# LFR_A_v2.net
KiCad netlist of a schematic drawn in Altium Designer
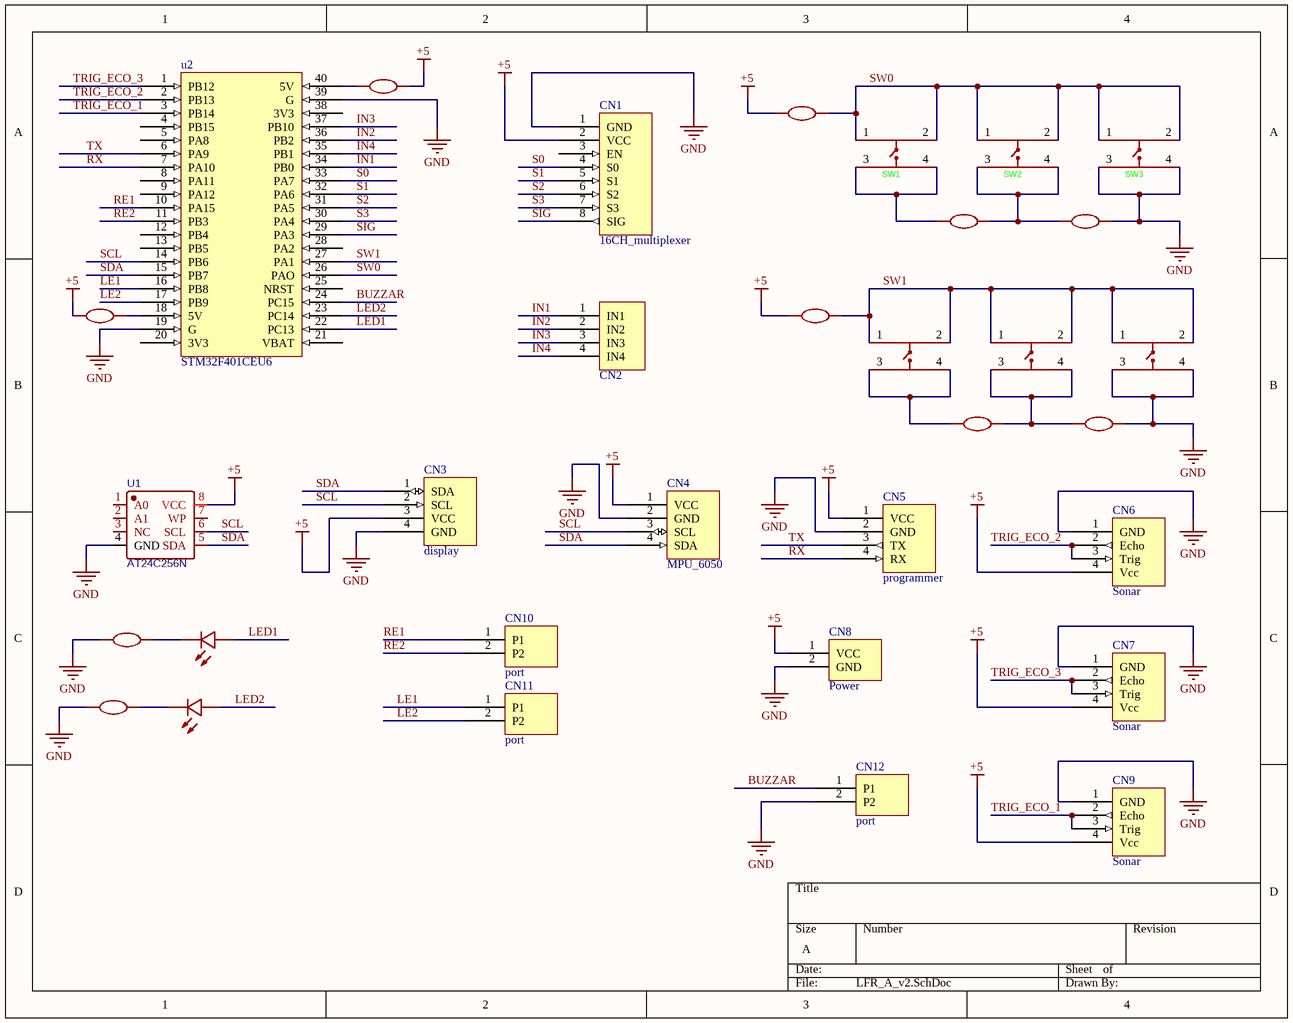
[diagram p0: LFR_A_v2.SchDoc]

(export (version "E")
  (design (tool "Eeschema 10.0.6"))
  (components
    (comp (ref "CN1")
      (value "16CH_multiplexer")
      (footprint "16CH_MUX")
      (libsource (lib "Schlib1") (part "16CH_multiplexer"))
    )
    (comp (ref "CN2") (value "M_Driver") (footprint "M_driver") (libsource (lib "Schlib1") (part "M_Driver")))
    (comp (ref "CN3") (value "display") (footprint "display") (libsource (lib "Schlib1") (part "display")))
    (comp (ref "CN4") (value "MPU_6050") (footprint "mpu_6050") (libsource (lib "Schlib1") (part "MPU_6050")))
    (comp (ref "CN5")
      (value "programmer")
      (footprint "Sonar")
      (libsource (lib "Schlib1") (part "programmer"))
    )
    (comp (ref "CN6") (value "Sonar") (footprint "Sonar") (libsource (lib "Schlib1") (part "Sonar")))
    (comp (ref "CN7") (value "Sonar") (footprint "Sonar") (libsource (lib "Schlib1") (part "Sonar")))
    (comp (ref "CN8") (value "Power") (footprint "power") (libsource (lib "Schlib1") (part "Power")))
    (comp (ref "CN9") (value "Sonar") (footprint "Sonar") (libsource (lib "Schlib1") (part "Sonar")))
    (comp (ref "CN10") (value "port") (footprint "power") (libsource (lib "Schlib1") (part "port")))
    (comp (ref "CN11") (value "port") (footprint "power") (libsource (lib "Schlib1") (part "port")))
    (comp (ref "CN12") (value "port") (footprint "power") (libsource (lib "Schlib1") (part "port")))
    (comp (ref "LED1")
      (value "333-2SURD/S530-A3")
      (footprint "LED-TH_BD5.9-P2.54-RD_RED")
      (fields (field (name "MANUFACTURER") "EVERLIGHT(亿光)"))
      (libsource (lib "Schlib1") (part "LED"))
    )
    (comp (ref "LED2")
      (value "333-2SURD/S530-A3")
      (footprint "LED-TH_BD5.9-P2.54-RD_RED")
      (fields (field (name "MANUFACTURER") "EVERLIGHT(亿光)"))
      (libsource (lib "Schlib1") (part "LED"))
    )
    (comp (ref "R1")
      (value "10kΩ")
      (footprint "regsistor")
      (fields
        (field (name "MANUFACTURER") "VISHAY(威世)")
        (field (name "MANUFACTURER PART") "MBB02070C1002FCT00")
        (field (name "TOLERANCE") "±1%")
      )
      (libsource (lib "Schlib1") (part "reg_10k"))
    )
    (comp (ref "R2")
      (value "10kΩ")
      (footprint "regsistor")
      (fields
        (field (name "MANUFACTURER") "VISHAY(威世)")
        (field (name "MANUFACTURER PART") "MBB02070C1002FCT00")
        (field (name "TOLERANCE") "±1%")
      )
      (libsource (lib "Schlib1") (part "reg_10k"))
    )
    (comp (ref "R3")
      (value "10kΩ")
      (footprint "regsistor")
      (fields
        (field (name "MANUFACTURER") "VISHAY(威世)")
        (field (name "MANUFACTURER PART") "MBB02070C1002FCT00")
        (field (name "TOLERANCE") "±1%")
      )
      (libsource (lib "Schlib1") (part "reg_10k"))
    )
    (comp (ref "R4")
      (value "10kΩ")
      (footprint "regsistor")
      (fields
        (field (name "MANUFACTURER") "VISHAY(威世)")
        (field (name "MANUFACTURER PART") "MBB02070C1002FCT00")
        (field (name "TOLERANCE") "±1%")
      )
      (libsource (lib "Schlib1") (part "reg_10k"))
    )
    (comp (ref "R5")
      (value "10kΩ")
      (footprint "regsistor")
      (fields
        (field (name "MANUFACTURER") "VISHAY(威世)")
        (field (name "MANUFACTURER PART") "MBB02070C1002FCT00")
        (field (name "TOLERANCE") "±1%")
      )
      (libsource (lib "Schlib1") (part "reg_10k"))
    )
    (comp (ref "R6")
      (value "10kΩ")
      (footprint "regsistor")
      (fields
        (field (name "MANUFACTURER") "VISHAY(威世)")
        (field (name "MANUFACTURER PART") "MBB02070C1002FCT00")
        (field (name "TOLERANCE") "±1%")
      )
      (libsource (lib "Schlib1") (part "reg_10k"))
    )
    (comp (ref "R7")
      (value "10kΩ")
      (footprint "regsistor")
      (fields
        (field (name "MANUFACTURER") "VISHAY(威世)")
        (field (name "MANUFACTURER PART") "MBB02070C1002FCT00")
        (field (name "TOLERANCE") "±1%")
      )
      (libsource (lib "Schlib1") (part "reg_10k"))
    )
    (comp (ref "R8")
      (value "10kΩ")
      (footprint "regsistor")
      (fields
        (field (name "MANUFACTURER") "VISHAY(威世)")
        (field (name "MANUFACTURER PART") "MBB02070C1002FCT00")
        (field (name "TOLERANCE") "±1%")
      )
      (libsource (lib "Schlib1") (part "reg_10k"))
    )
    (comp (ref "R9")
      (value "10kΩ")
      (footprint "regsistor")
      (fields
        (field (name "MANUFACTURER") "VISHAY(威世)")
        (field (name "MANUFACTURER PART") "MBB02070C1002FCT00")
        (field (name "TOLERANCE") "±1%")
      )
      (libsource (lib "Schlib1") (part "reg_10k"))
    )
    (comp (ref "R10")
      (value "10kΩ")
      (footprint "regsistor")
      (fields
        (field (name "MANUFACTURER") "VISHAY(威世)")
        (field (name "MANUFACTURER PART") "MBB02070C1002FCT00")
        (field (name "TOLERANCE") "±1%")
      )
      (libsource (lib "Schlib1") (part "reg_10k"))
    )
    (comp (ref "SW1")
      (value "1825910-7")
      (footprint "button")
      (fields (field (name "MANUFACTURER") "TE Connectivity(泰科电子)"))
      (libsource (lib "Schlib1") (part "button"))
    )
    (comp (ref "SW2")
      (value "1825910-7")
      (footprint "button")
      (fields (field (name "MANUFACTURER") "TE Connectivity(泰科电子)"))
      (libsource (lib "Schlib1") (part "button"))
    )
    (comp (ref "SW3")
      (value "1825910-7")
      (footprint "button")
      (fields (field (name "MANUFACTURER") "TE Connectivity(泰科电子)"))
      (libsource (lib "Schlib1") (part "button"))
    )
    (comp (ref "SW4")
      (value "1825910-7")
      (footprint "button")
      (fields (field (name "MANUFACTURER") "TE Connectivity(泰科电子)"))
      (libsource (lib "Schlib1") (part "button"))
    )
    (comp (ref "SW5")
      (value "1825910-7")
      (footprint "button")
      (fields (field (name "MANUFACTURER") "TE Connectivity(泰科电子)"))
      (libsource (lib "Schlib1") (part "button"))
    )
    (comp (ref "SW6")
      (value "1825910-7")
      (footprint "button")
      (fields (field (name "MANUFACTURER") "TE Connectivity(泰科电子)"))
      (libsource (lib "Schlib1") (part "button"))
    )
    (comp (ref "U1")
      (value "AT24C256N")
      (footprint "DIP-8_L9.8-W6.6-P2.54-LS7.6-BL")
      (fields (field (name "MANUFACTURER") "HGSEMI(华冠)") (field (name "CONTRIBUTOR") "LCSC"))
      (libsource (lib "Schlib1") (part "AT24C256N"))
    )
    (comp (ref "u2")
      (value "STM32F401CEU6")
      (footprint "STM32F411CE")
      (libsource (lib "Schlib1") (part "STM32F401CEU6"))
    )
  )
  (nets
    (net (code "1") (name "+5") (class "Default")
      (node (ref "CN1") (pin "2") (pinfunction "VCC_2") (pintype "power_in"))
      (node (ref "CN3") (pin "3") (pinfunction "VCC_3") (pintype "power_in"))
      (node (ref "CN4") (pin "1") (pinfunction "VCC_1") (pintype "power_in"))
      (node (ref "CN5") (pin "1") (pinfunction "VCC_1") (pintype "power_in"))
      (node (ref "CN6") (pin "4") (pinfunction "Vcc_4") (pintype "power_in"))
      (node (ref "CN7") (pin "4") (pinfunction "Vcc_4") (pintype "power_in"))
      (node (ref "CN8") (pin "1") (pinfunction "VCC_1") (pintype "power_in"))
      (node (ref "CN9") (pin "4") (pinfunction "Vcc_4") (pintype "power_in"))
      (node (ref "R1") (pin "1") (pinfunction "1_1") (pintype "passive"))
      (node (ref "R4") (pin "1") (pinfunction "1_1") (pintype "passive"))
      (node (ref "R7") (pin "2") (pinfunction "2_2") (pintype "passive"))
      (node (ref "R8") (pin "2") (pinfunction "2_2") (pintype "passive"))
      (node (ref "U1") (pin "8") (pinfunction "VCC_8") (pintype "passive"))
    )
    (net (code "2") (name "/BUZZAR") (class "Default")
      (node (ref "CN12") (pin "1") (pinfunction "P1_1") (pintype "passive"))
      (node (ref "u2") (pin "24") (pinfunction "PC15_24") (pintype "input"))
    )
    (net (code "3") (name "/IN1") (class "Default")
      (node (ref "CN2") (pin "1") (pinfunction "IN1_1") (pintype "passive"))
      (node (ref "u2") (pin "34") (pinfunction "PB0_34") (pintype "input"))
    )
    (net (code "4") (name "/IN2") (class "Default")
      (node (ref "CN2") (pin "2") (pinfunction "IN2_2") (pintype "passive"))
      (node (ref "u2") (pin "36") (pinfunction "PB2_36") (pintype "input"))
    )
    (net (code "5") (name "/IN3") (class "Default")
      (node (ref "CN2") (pin "3") (pinfunction "IN3_3") (pintype "passive"))
      (node (ref "u2") (pin "37") (pinfunction "PB10_37") (pintype "input"))
    )
    (net (code "6") (name "/IN4") (class "Default")
      (node (ref "CN2") (pin "4") (pinfunction "IN4_4") (pintype "passive"))
      (node (ref "u2") (pin "35") (pinfunction "PB1_35") (pintype "input"))
    )
    (net (code "7") (name "/LE1") (class "Default")
      (node (ref "CN11") (pin "1") (pinfunction "P1_1") (pintype "passive"))
      (node (ref "u2") (pin "16") (pinfunction "PB8_16") (pintype "input"))
    )
    (net (code "8") (name "/LE2") (class "Default")
      (node (ref "CN11") (pin "2") (pinfunction "P2_2") (pintype "passive"))
      (node (ref "u2") (pin "17") (pinfunction "PB9_17") (pintype "input"))
    )
    (net (code "9") (name "/LED1") (class "Default")
      (node (ref "LED1") (pin "2") (pinfunction "A_2") (pintype "passive"))
      (node (ref "u2") (pin "22") (pinfunction "PC13_22") (pintype "input"))
    )
    (net (code "10") (name "/LED2") (class "Default")
      (node (ref "LED2") (pin "2") (pinfunction "A_2") (pintype "passive"))
      (node (ref "u2") (pin "23") (pinfunction "PC14_23") (pintype "input"))
    )
    (net (code "11") (name "/RE1") (class "Default")
      (node (ref "CN10") (pin "1") (pinfunction "P1_1") (pintype "passive"))
      (node (ref "u2") (pin "10") (pinfunction "PA15_10") (pintype "input"))
    )
    (net (code "12") (name "/RE2") (class "Default")
      (node (ref "CN10") (pin "2") (pinfunction "P2_2") (pintype "passive"))
      (node (ref "u2") (pin "11") (pinfunction "PB3_11") (pintype "input"))
    )
    (net (code "13") (name "/RX") (class "Default")
      (node (ref "CN5") (pin "4") (pinfunction "RX_4") (pintype "input"))
      (node (ref "u2") (pin "7") (pinfunction "PA10_7") (pintype "input"))
    )
    (net (code "14") (name "/S0") (class "Default")
      (node (ref "CN1") (pin "4") (pinfunction "S0_4") (pintype "input"))
      (node (ref "u2") (pin "33") (pinfunction "PA7_33") (pintype "input"))
    )
    (net (code "15") (name "/S1") (class "Default")
      (node (ref "CN1") (pin "5") (pinfunction "S1_5") (pintype "input"))
      (node (ref "u2") (pin "32") (pinfunction "PA6_32") (pintype "input"))
    )
    (net (code "16") (name "/S2") (class "Default")
      (node (ref "CN1") (pin "6") (pinfunction "S2_6") (pintype "input"))
      (node (ref "u2") (pin "31") (pinfunction "PA5_31") (pintype "input"))
    )
    (net (code "17") (name "/S3") (class "Default")
      (node (ref "CN1") (pin "7") (pinfunction "S3_7") (pintype "input"))
      (node (ref "u2") (pin "30") (pinfunction "PA4_30") (pintype "input"))
    )
    (net (code "18") (name "/SCL") (class "Default")
      (node (ref "CN3") (pin "2") (pinfunction "SCL_2") (pintype "input"))
      (node (ref "CN4") (pin "3") (pinfunction "SCL_3") (pintype "bidirectional"))
      (node (ref "U1") (pin "6") (pinfunction "SCL_6") (pintype "passive"))
      (node (ref "u2") (pin "14") (pinfunction "PB6_14") (pintype "input"))
    )
    (net (code "19") (name "/SDA") (class "Default")
      (node (ref "CN3") (pin "1") (pinfunction "SDA_1") (pintype "bidirectional"))
      (node (ref "CN4") (pin "4") (pinfunction "SDA_4") (pintype "input"))
      (node (ref "U1") (pin "5") (pinfunction "SDA_5") (pintype "passive"))
      (node (ref "u2") (pin "15") (pinfunction "PB7_15") (pintype "input"))
    )
    (net (code "20") (name "/SIG") (class "Default")
      (node (ref "CN1") (pin "8") (pinfunction "SIG_8") (pintype "output"))
      (node (ref "u2") (pin "29") (pinfunction "PA3_29") (pintype "input"))
    )
    (net (code "21") (name "/SW0") (class "Default")
      (node (ref "R1") (pin "2") (pinfunction "2_2") (pintype "passive"))
      (node (ref "SW1") (pin "1") (pinfunction "1_1") (pintype "passive"))
      (node (ref "SW1") (pin "2") (pinfunction "2_2") (pintype "passive"))
      (node (ref "SW2") (pin "1") (pinfunction "1_1") (pintype "passive"))
      (node (ref "SW2") (pin "2") (pinfunction "2_2") (pintype "passive"))
      (node (ref "SW3") (pin "1") (pinfunction "1_1") (pintype "passive"))
      (node (ref "SW3") (pin "2") (pinfunction "2_2") (pintype "passive"))
      (node (ref "u2") (pin "26") (pinfunction "PAO_26") (pintype "input"))
    )
    (net (code "22") (name "/SW1") (class "Default")
      (node (ref "R4") (pin "2") (pinfunction "2_2") (pintype "passive"))
      (node (ref "SW4") (pin "1") (pinfunction "1_1") (pintype "passive"))
      (node (ref "SW4") (pin "2") (pinfunction "2_2") (pintype "passive"))
      (node (ref "SW5") (pin "1") (pinfunction "1_1") (pintype "passive"))
      (node (ref "SW5") (pin "2") (pinfunction "2_2") (pintype "passive"))
      (node (ref "SW6") (pin "1") (pinfunction "1_1") (pintype "passive"))
      (node (ref "SW6") (pin "2") (pinfunction "2_2") (pintype "passive"))
      (node (ref "u2") (pin "27") (pinfunction "PA1_27") (pintype "input"))
    )
    (net (code "23") (name "/TRIG_ECO_1") (class "Default")
      (node (ref "CN9") (pin "2") (pinfunction "Echo_2") (pintype "output"))
      (node (ref "CN9") (pin "3") (pinfunction "Trig_3") (pintype "input"))
      (node (ref "u2") (pin "3") (pinfunction "PB14_3") (pintype "input"))
    )
    (net (code "24") (name "/TRIG_ECO_2") (class "Default")
      (node (ref "CN6") (pin "2") (pinfunction "Echo_2") (pintype "output"))
      (node (ref "CN6") (pin "3") (pinfunction "Trig_3") (pintype "input"))
      (node (ref "u2") (pin "2") (pinfunction "PB13_2") (pintype "input"))
    )
    (net (code "25") (name "/TRIG_ECO_3") (class "Default")
      (node (ref "CN7") (pin "2") (pinfunction "Echo_2") (pintype "output"))
      (node (ref "CN7") (pin "3") (pinfunction "Trig_3") (pintype "input"))
      (node (ref "u2") (pin "1") (pinfunction "PB12_1") (pintype "input"))
    )
    (net (code "26") (name "/TX") (class "Default")
      (node (ref "CN5") (pin "3") (pinfunction "TX_3") (pintype "output"))
      (node (ref "u2") (pin "6") (pinfunction "PA9_6") (pintype "input"))
    )
    (net (code "27") (name "GND") (class "Default")
      (node (ref "CN1") (pin "1") (pinfunction "GND_1") (pintype "power_in"))
      (node (ref "CN12") (pin "2") (pinfunction "P2_2") (pintype "passive"))
      (node (ref "CN3") (pin "4") (pinfunction "GND_4") (pintype "power_in"))
      (node (ref "CN4") (pin "2") (pinfunction "GND_2") (pintype "power_in"))
      (node (ref "CN5") (pin "2") (pinfunction "GND_2") (pintype "power_in"))
      (node (ref "CN6") (pin "1") (pinfunction "GND_1") (pintype "power_in"))
      (node (ref "CN7") (pin "1") (pinfunction "GND_1") (pintype "power_in"))
      (node (ref "CN8") (pin "2") (pinfunction "GND_2") (pintype "power_in"))
      (node (ref "CN9") (pin "1") (pinfunction "GND_1") (pintype "power_in"))
      (node (ref "R10") (pin "1") (pinfunction "1_1") (pintype "passive"))
      (node (ref "R3") (pin "2") (pinfunction "2_2") (pintype "passive"))
      (node (ref "R6") (pin "2") (pinfunction "2_2") (pintype "passive"))
      (node (ref "R9") (pin "1") (pinfunction "1_1") (pintype "passive"))
      (node (ref "SW3") (pin "3") (pinfunction "3_3") (pintype "passive"))
      (node (ref "SW3") (pin "4") (pinfunction "4_4") (pintype "passive"))
      (node (ref "SW6") (pin "3") (pinfunction "3_3") (pintype "passive"))
      (node (ref "SW6") (pin "4") (pinfunction "4_4") (pintype "passive"))
      (node (ref "U1") (pin "4") (pinfunction "GND_4") (pintype "passive"))
      (node (ref "u2") (pin "19") (pinfunction "G_19") (pintype "input"))
      (node (ref "u2") (pin "39") (pinfunction "G_39") (pintype "input"))
    )
    (net (code "28") (name "Net-(LED1-C)") (class "Default")
      (node (ref "LED1") (pin "1") (pinfunction "C_1") (pintype "passive"))
      (node (ref "R9") (pin "2") (pinfunction "2_2") (pintype "passive"))
    )
    (net (code "29") (name "Net-(LED2-C)") (class "Default")
      (node (ref "LED2") (pin "1") (pinfunction "C_1") (pintype "passive"))
      (node (ref "R10") (pin "2") (pinfunction "2_2") (pintype "passive"))
    )
    (net (code "30") (name "Net-(R2-Pad1)") (class "Default")
      (node (ref "R2") (pin "1") (pinfunction "1_1") (pintype "passive"))
      (node (ref "SW1") (pin "3") (pinfunction "3_3") (pintype "passive"))
      (node (ref "SW1") (pin "4") (pinfunction "4_4") (pintype "passive"))
    )
    (net (code "31") (name "Net-(R2-Pad2)") (class "Default")
      (node (ref "R2") (pin "2") (pinfunction "2_2") (pintype "passive"))
      (node (ref "R3") (pin "1") (pinfunction "1_1") (pintype "passive"))
      (node (ref "SW2") (pin "3") (pinfunction "3_3") (pintype "passive"))
      (node (ref "SW2") (pin "4") (pinfunction "4_4") (pintype "passive"))
    )
    (net (code "32") (name "Net-(R5-Pad1)") (class "Default")
      (node (ref "R5") (pin "1") (pinfunction "1_1") (pintype "passive"))
      (node (ref "SW4") (pin "3") (pinfunction "3_3") (pintype "passive"))
      (node (ref "SW4") (pin "4") (pinfunction "4_4") (pintype "passive"))
    )
    (net (code "33") (name "Net-(R5-Pad2)") (class "Default")
      (node (ref "R5") (pin "2") (pinfunction "2_2") (pintype "passive"))
      (node (ref "R6") (pin "1") (pinfunction "1_1") (pintype "passive"))
      (node (ref "SW5") (pin "3") (pinfunction "3_3") (pintype "passive"))
      (node (ref "SW5") (pin "4") (pinfunction "4_4") (pintype "passive"))
    )
    (net (code "34") (name "Net-(R7-Pad1)") (class "Default")
      (node (ref "R7") (pin "1") (pinfunction "1_1") (pintype "passive"))
      (node (ref "u2") (pin "40") (pinfunction "5V_40") (pintype "input"))
    )
    (net (code "35") (name "Net-(R8-Pad1)") (class "Default")
      (node (ref "R8") (pin "1") (pinfunction "1_1") (pintype "passive"))
      (node (ref "u2") (pin "18") (pinfunction "5V_18") (pintype "input"))
    )
    (net (code "36") (name "unconnected-(CN1-EN-Pad3)") (class "Default")
      (node (ref "CN1") (pin "3") (pinfunction "EN_3") (pintype "input"))
    )
    (net (code "37") (name "unconnected-(U1-A0-Pad1)") (class "Default")
      (node (ref "U1") (pin "1") (pinfunction "A0_1") (pintype "passive"))
    )
    (net (code "38") (name "unconnected-(U1-A1-Pad2)") (class "Default")
      (node (ref "U1") (pin "2") (pinfunction "A1_2") (pintype "passive"))
    )
    (net (code "39") (name "unconnected-(U1-NC-Pad3)") (class "Default")
      (node (ref "U1") (pin "3") (pinfunction "NC_3") (pintype "passive"))
    )
    (net (code "40") (name "unconnected-(U1-WP-Pad7)") (class "Default")
      (node (ref "U1") (pin "7") (pinfunction "WP_7") (pintype "passive"))
    )
    (net (code "41") (name "unconnected-(u2-3V3-Pad20)") (class "Default")
      (node (ref "u2") (pin "20") (pinfunction "3V3_20") (pintype "input"))
    )
    (net (code "42") (name "unconnected-(u2-3V3-Pad38)") (class "Default")
      (node (ref "u2") (pin "38") (pinfunction "3V3_38") (pintype "input"))
    )
    (net (code "43") (name "unconnected-(u2-NRST-Pad25)") (class "Default")
      (node (ref "u2") (pin "25") (pinfunction "NRST_25") (pintype "input"))
    )
    (net (code "44") (name "unconnected-(u2-PA2-Pad28)") (class "Default")
      (node (ref "u2") (pin "28") (pinfunction "PA2_28") (pintype "input"))
    )
    (net (code "45") (name "unconnected-(u2-PA8-Pad5)") (class "Default")
      (node (ref "u2") (pin "5") (pinfunction "PA8_5") (pintype "input"))
    )
    (net (code "46") (name "unconnected-(u2-PA11-Pad8)") (class "Default")
      (node (ref "u2") (pin "8") (pinfunction "PA11_8") (pintype "input"))
    )
    (net (code "47") (name "unconnected-(u2-PA12-Pad9)") (class "Default")
      (node (ref "u2") (pin "9") (pinfunction "PA12_9") (pintype "input"))
    )
    (net (code "48") (name "unconnected-(u2-PB4-Pad12)") (class "Default")
      (node (ref "u2") (pin "12") (pinfunction "PB4_12") (pintype "input"))
    )
    (net (code "49") (name "unconnected-(u2-PB5-Pad13)") (class "Default")
      (node (ref "u2") (pin "13") (pinfunction "PB5_13") (pintype "input"))
    )
    (net (code "50") (name "unconnected-(u2-PB15-Pad4)") (class "Default")
      (node (ref "u2") (pin "4") (pinfunction "PB15_4") (pintype "input"))
    )
    (net (code "51") (name "unconnected-(u2-VBAT-Pad21)") (class "Default")
      (node (ref "u2") (pin "21") (pinfunction "VBAT_21") (pintype "input"))
    )
  )
)
